# MCU.net
KiCad netlist of a schematic drawn in Altium Designer
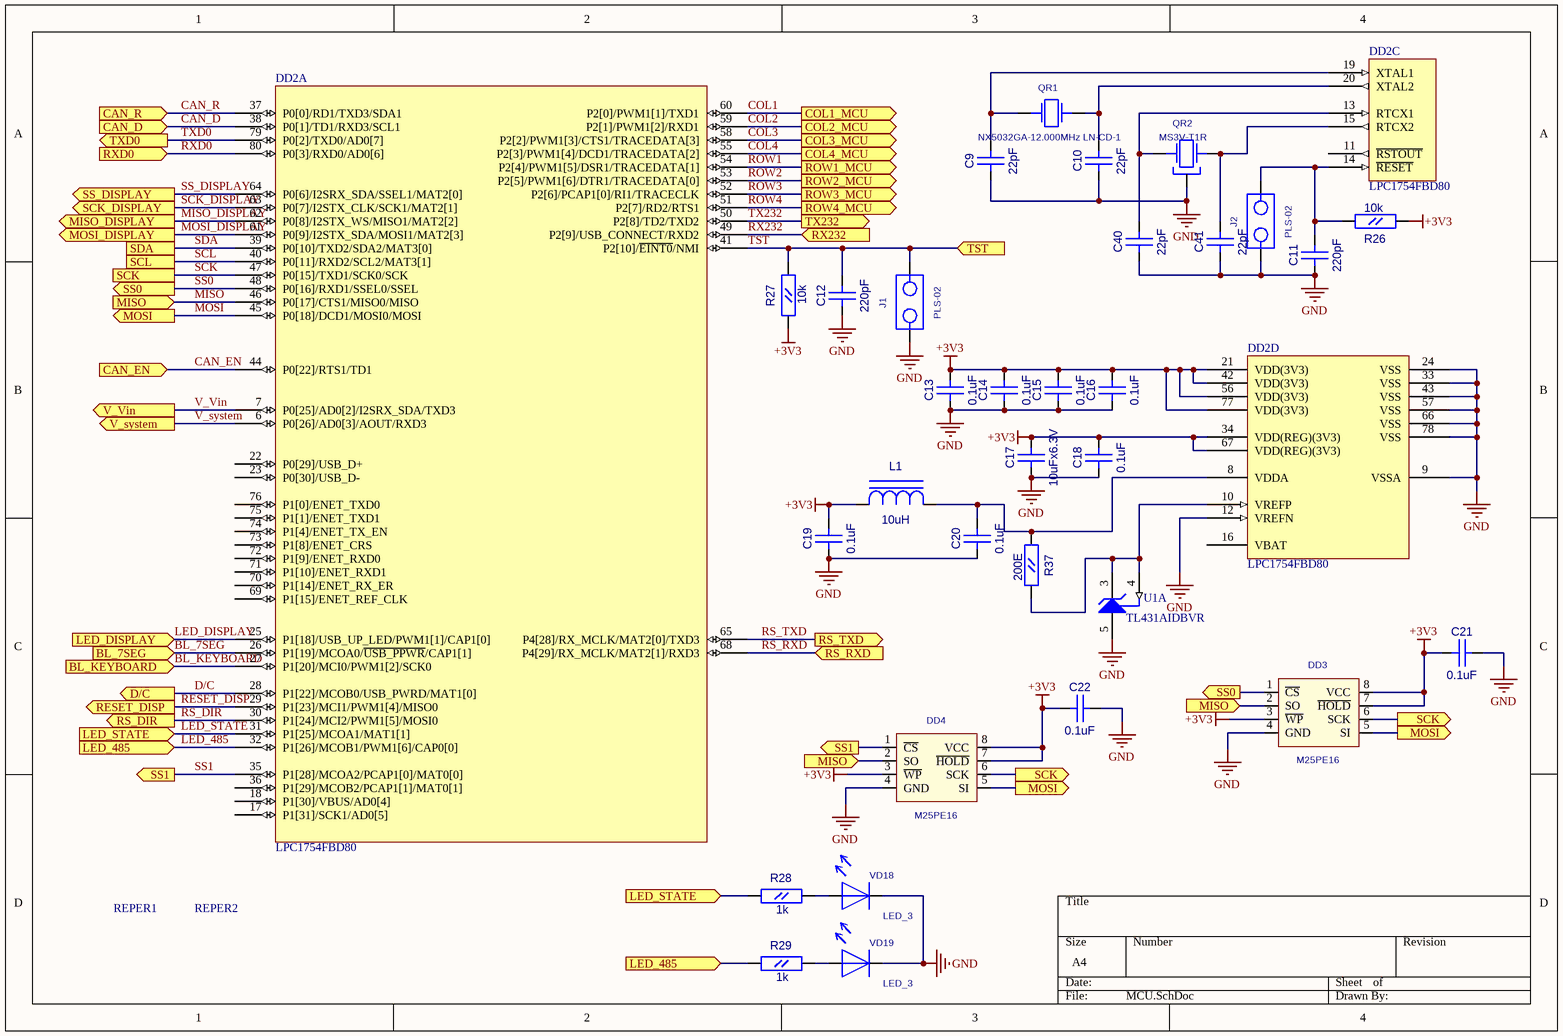
[diagram p0: MCU.SchDoc]

(export (version "E")
  (design (tool "Eeschema 10.0.6"))
  (components
    (comp (ref "C9")
      (value "22pF")
      (footprint "CC0603")
      (description "CC0603")
      (libsource (lib "gprs_modem_2") (part "CC0603"))
    )
    (comp (ref "C10")
      (value "22pF")
      (footprint "CC0603")
      (description "CC0603")
      (libsource (lib "gprs_modem_2") (part "CC0603"))
    )
    (comp (ref "C11")
      (value "220pF")
      (footprint "CC0603")
      (description "CC0603")
      (libsource (lib "gprs_modem_2") (part "CC0603"))
    )
    (comp (ref "C12")
      (value "220pF")
      (footprint "CC0603")
      (description "CC0603")
      (libsource (lib "gprs_modem_2") (part "CC0603"))
    )
    (comp (ref "C13")
      (value "0.1uF")
      (footprint "CC0603")
      (description "CC0603")
      (libsource (lib "gprs_modem_2") (part "CC0603"))
    )
    (comp (ref "C14")
      (value "0.1uF")
      (footprint "CC0603")
      (description "CC0603")
      (libsource (lib "gprs_modem_2") (part "CC0603"))
    )
    (comp (ref "C15")
      (value "0.1uF")
      (footprint "CC0603")
      (description "CC0603")
      (libsource (lib "gprs_modem_2") (part "CC0603"))
    )
    (comp (ref "C16")
      (value "0.1uF")
      (footprint "CC0603")
      (description "CC0603")
      (libsource (lib "gprs_modem_2") (part "CC0603"))
    )
    (comp (ref "C17")
      (value "10uFx6.3V")
      (footprint "CC0805")
      (description "CC0805")
      (libsource (lib "gprs_modem_2") (part "CC0805"))
    )
    (comp (ref "C18")
      (value "0.1uF")
      (footprint "CC0603")
      (description "CC0603")
      (libsource (lib "gprs_modem_2") (part "CC0603"))
    )
    (comp (ref "C19")
      (value "0.1uF")
      (footprint "CC0603")
      (description "CC0603")
      (libsource (lib "gprs_modem_2") (part "CC0603"))
    )
    (comp (ref "C20")
      (value "0.1uF")
      (footprint "CC0603")
      (description "CC0603")
      (libsource (lib "gprs_modem_2") (part "CC0603"))
    )
    (comp (ref "C21")
      (value "0.1uF")
      (footprint "CC0603")
      (description "CC0603")
      (libsource (lib "gprs_modem_2") (part "CC0603"))
    )
    (comp (ref "C22")
      (value "0.1uF")
      (footprint "CC0603")
      (description "CC0603")
      (libsource (lib "gprs_modem_2") (part "CC0603"))
    )
    (comp (ref "C40")
      (value "22pF")
      (footprint "CC0603")
      (description "CC0603")
      (libsource (lib "gprs_modem_2") (part "CC0603"))
    )
    (comp (ref "C41")
      (value "22pF")
      (footprint "CC0603")
      (description "CC0603")
      (libsource (lib "gprs_modem_2") (part "CC0603"))
    )
    (comp (ref "DD2")
      (value "LPC1754FBD80")
      (footprint "TQFP-80_0.5")
      (description "Cortex -M3 32-Bit Microcontroller, 128KB Flash, 64KB RAM, 800-Lead LQFP")
      (libsource (lib "gprs_modem_2") (part "LPC1754FBD80"))
    )
    (comp (ref "DD3")
      (value "M25PE16")
      (footprint "EIAJ_SO8")
      (description "S25FL016A0LMFI01")
      (libsource (lib "gprs_modem_2") (part "S25FL016A0LMFI01"))
    )
    (comp (ref "DD4")
      (value "M25PE16")
      (footprint "EIAJ_SO8")
      (description "S25FL016A0LMFI01")
      (libsource (lib "gprs_modem_2") (part "S25FL016A0LMFI01"))
    )
    (comp (ref "J1") (value "PLS-02") (footprint "PLS-02") (libsource (lib "gprs_modem_2") (part "PLS-02")))
    (comp (ref "J2") (value "PLS-02") (footprint "PLS-02") (libsource (lib "gprs_modem_2") (part "PLS-02")))
    (comp (ref "L1")
      (value "10uH")
      (footprint "L0603")
      (description "L0603")
      (libsource (lib "gprs_modem_2") (part "L0603"))
    )
    (comp (ref "QR1")
      (value "NX5032GA-12.000MHz LN-CD-1")
      (footprint "AC5032_2")
      (description "AC5032/2")
      (libsource (lib "gprs_modem_2") (part "AC5032_2"))
    )
    (comp (ref "QR2")
      (value "MS3V-T1R")
      (footprint "MS3V-T1R")
      (description "CRYSTAL_32768 Hz")
      (libsource (lib "gprs_modem_2") (part "MS3V-T1R"))
    )
    (comp (ref "R26")
      (value "10k")
      (footprint "RC0603")
      (description "RC0603")
      (libsource (lib "gprs_modem_2") (part "RC0603"))
    )
    (comp (ref "R27")
      (value "10k")
      (footprint "RC0603")
      (description "RC0603")
      (libsource (lib "gprs_modem_2") (part "RC0603"))
    )
    (comp (ref "R28")
      (value "1k")
      (footprint "RC0603")
      (description "RC0603")
      (libsource (lib "gprs_modem_2") (part "RC0603"))
    )
    (comp (ref "R29")
      (value "1k")
      (footprint "RC0603")
      (description "RC0603")
      (libsource (lib "gprs_modem_2") (part "RC0603"))
    )
    (comp (ref "R37")
      (value "200E")
      (footprint "RC0603")
      (description "RC0603")
      (libsource (lib "gprs_modem_2") (part "RC0603"))
    )
    (comp (ref "REPER1")
      (value "REPER1.2")
      (footprint "REPER1.2")
      (libsource (lib "gprs_modem") (part "REPER1.2"))
    )
    (comp (ref "REPER2")
      (value "REPER1.2")
      (footprint "REPER1.2")
      (libsource (lib "gprs_modem") (part "REPER1.2"))
    )
    (comp (ref "U1")
      (value "TL431AIDBVR")
      (footprint "TI-DBV5_N")
      (fields (field (name "MANUFACTURER") "Texas Instruments"))
      (libsource (lib "TI Power Management Shunt Voltage Reference") (part "TL431AIDBVR"))
    )
    (comp (ref "VD18") (value "LED_3") (footprint "LED3") (libsource (lib "gprs_modem_2") (part "LED_3")))
    (comp (ref "VD19") (value "LED_3") (footprint "LED3") (libsource (lib "gprs_modem_2") (part "LED_3")))
  )
  (nets
    (net (code "1") (name "+3V3") (class "Default")
      (node (ref "C13") (pin "2") (pinfunction "B_2") (pintype "passive"))
      (node (ref "C14") (pin "2") (pinfunction "B_2") (pintype "passive"))
      (node (ref "C15") (pin "2") (pinfunction "B_2") (pintype "passive"))
      (node (ref "C16") (pin "2") (pinfunction "B_2") (pintype "passive"))
      (node (ref "C17") (pin "2") (pinfunction "B_2") (pintype "passive"))
      (node (ref "C18") (pin "2") (pinfunction "B_2") (pintype "passive"))
      (node (ref "C19") (pin "2") (pinfunction "B_2") (pintype "passive"))
      (node (ref "C21") (pin "1") (pinfunction "A_1") (pintype "passive"))
      (node (ref "C22") (pin "1") (pinfunction "A_1") (pintype "passive"))
      (node (ref "DD2") (pin "21") (pinfunction "VDD(3V3)_21") (pintype "power_in"))
      (node (ref "DD2") (pin "34") (pinfunction "VDD(REG)(3V3)_34") (pintype "power_in"))
      (node (ref "DD2") (pin "42") (pinfunction "VDD(3V3)_42") (pintype "power_in"))
      (node (ref "DD2") (pin "56") (pinfunction "VDD(3V3)_56") (pintype "power_in"))
      (node (ref "DD2") (pin "67") (pinfunction "VDD(REG)(3V3)_67") (pintype "power_in"))
      (node (ref "DD2") (pin "77") (pinfunction "VDD(3V3)_77") (pintype "power_in"))
      (node (ref "DD3") (pin "3") (pinfunction "~{WP}_3") (pintype "passive"))
      (node (ref "DD3") (pin "7") (pinfunction "~{HOLD}_7") (pintype "passive"))
      (node (ref "DD3") (pin "8") (pinfunction "VCC_8") (pintype "passive"))
      (node (ref "DD4") (pin "3") (pinfunction "~{WP}_3") (pintype "passive"))
      (node (ref "DD4") (pin "7") (pinfunction "~{HOLD}_7") (pintype "passive"))
      (node (ref "DD4") (pin "8") (pinfunction "VCC_8") (pintype "passive"))
      (node (ref "L1") (pin "1") (pinfunction "A_1") (pintype "passive"))
      (node (ref "R26") (pin "1") (pinfunction "A_1") (pintype "passive"))
      (node (ref "R27") (pin "1") (pinfunction "A_1") (pintype "passive"))
    )
    (net (code "2") (name "/BL_7SEG") (class "Default")
      (node (ref "DD2") (pin "26") (pinfunction "P1[19]/MCOA0/~{USB_PPWR}/CAP1[1]_26") (pintype "bidirectional"))
    )
    (net (code "3") (name "/BL_KEYBOARD") (class "Default")
      (node (ref "DD2") (pin "27") (pinfunction "P1[20]/MCI0/PWM1[2]/SCK0_27") (pintype "bidirectional"))
    )
    (net (code "4") (name "/CAN_D") (class "Default")
      (node (ref "DD2") (pin "38") (pinfunction "P0[1]/TD1/RXD3/SCL1_38") (pintype "bidirectional"))
    )
    (net (code "5") (name "/CAN_EN") (class "Default")
      (node (ref "DD2") (pin "44") (pinfunction "P0[22]/RTS1/TD1_44") (pintype "bidirectional"))
    )
    (net (code "6") (name "/CAN_R") (class "Default")
      (node (ref "DD2") (pin "37") (pinfunction "P0[0]/RD1/TXD3/SDA1_37") (pintype "bidirectional"))
    )
    (net (code "7") (name "/COL1") (class "Default")
      (node (ref "DD2") (pin "60") (pinfunction "P2[0]/PWM1[1]/TXD1_60") (pintype "bidirectional"))
    )
    (net (code "8") (name "/COL2") (class "Default")
      (node (ref "DD2") (pin "59") (pinfunction "P2[1]/PWM1[2]/RXD1_59") (pintype "bidirectional"))
    )
    (net (code "9") (name "/COL3") (class "Default")
      (node (ref "DD2") (pin "58") (pinfunction "P2[2]/PWM1[3]/CTS1/TRACEDATA[3]_58") (pintype "bidirectional"))
    )
    (net (code "10") (name "/COL4") (class "Default")
      (node (ref "DD2") (pin "55") (pinfunction "P2[3]/PWM1[4]/DCD1/TRACEDATA[2]_55") (pintype "bidirectional"))
    )
    (net (code "11") (name "/D{slash}C") (class "Default")
      (node (ref "DD2") (pin "28") (pinfunction "P1[22]/MCOB0/USB_PWRD/MAT1[0]_28") (pintype "bidirectional"))
    )
    (net (code "12") (name "/LED_485") (class "Default")
      (node (ref "DD2") (pin "32") (pinfunction "P1[26]/MCOB1/PWM1[6]/CAP0[0]_32") (pintype "bidirectional"))
      (node (ref "R29") (pin "1") (pinfunction "A_1") (pintype "passive"))
    )
    (net (code "13") (name "/LED_DISPLAY") (class "Default")
      (node (ref "DD2") (pin "25") (pinfunction "P1[18]/USB_UP_LED/PWM1[1]/CAP1[0]_25") (pintype "bidirectional"))
    )
    (net (code "14") (name "/LED_STATE") (class "Default")
      (node (ref "DD2") (pin "31") (pinfunction "P1[25]/MCOA1/MAT1[1]_31") (pintype "bidirectional"))
      (node (ref "R28") (pin "1") (pinfunction "A_1") (pintype "passive"))
    )
    (net (code "15") (name "/MISO") (class "Default")
      (node (ref "DD2") (pin "46") (pinfunction "P0[17]/CTS1/MISO0/MISO_46") (pintype "bidirectional"))
      (node (ref "DD3") (pin "2") (pinfunction "SO_2") (pintype "passive"))
      (node (ref "DD4") (pin "2") (pinfunction "SO_2") (pintype "passive"))
    )
    (net (code "16") (name "/MISO_DISPLAY") (class "Default")
      (node (ref "DD2") (pin "62") (pinfunction "P0[8]/I2STX_WS/MISO1/MAT2[2]_62") (pintype "bidirectional"))
    )
    (net (code "17") (name "/MOSI") (class "Default")
      (node (ref "DD2") (pin "45") (pinfunction "P0[18]/DCD1/MOSI0/MOSI_45") (pintype "bidirectional"))
      (node (ref "DD3") (pin "5") (pinfunction "SI_5") (pintype "passive"))
      (node (ref "DD4") (pin "5") (pinfunction "SI_5") (pintype "passive"))
    )
    (net (code "18") (name "/MOSI_DISPLAY") (class "Default")
      (node (ref "DD2") (pin "61") (pinfunction "P0[9]/I2STX_SDA/MOSI1/MAT2[3]_61") (pintype "bidirectional"))
    )
    (net (code "19") (name "/RESET_DISP") (class "Default")
      (node (ref "DD2") (pin "29") (pinfunction "P1[23]/MCI1/PWM1[4]/MISO0_29") (pintype "bidirectional"))
    )
    (net (code "20") (name "/ROW1") (class "Default")
      (node (ref "DD2") (pin "54") (pinfunction "P2[4]/PWM1[5]/DSR1/TRACEDATA[1]_54") (pintype "bidirectional"))
    )
    (net (code "21") (name "/ROW2") (class "Default")
      (node (ref "DD2") (pin "53") (pinfunction "P2[5]/PWM1[6]/DTR1/TRACEDATA[0]_53") (pintype "bidirectional"))
    )
    (net (code "22") (name "/ROW3") (class "Default")
      (node (ref "DD2") (pin "52") (pinfunction "P2[6]/PCAP1[0]/RI1/TRACECLK_52") (pintype "bidirectional"))
    )
    (net (code "23") (name "/ROW4") (class "Default")
      (node (ref "DD2") (pin "51") (pinfunction "P2[7]/RD2/RTS1_51") (pintype "bidirectional"))
    )
    (net (code "24") (name "/RS_DIR") (class "Default")
      (node (ref "DD2") (pin "30") (pinfunction "P1[24]/MCI2/PWM1[5]/MOSI0_30") (pintype "bidirectional"))
    )
    (net (code "25") (name "/RS_RXD") (class "Default")
      (node (ref "DD2") (pin "68") (pinfunction "P4[29]/RX_MCLK/MAT2[1]/RXD3_68") (pintype "bidirectional"))
    )
    (net (code "26") (name "/RS_TXD") (class "Default")
      (node (ref "DD2") (pin "65") (pinfunction "P4[28]/RX_MCLK/MAT2[0]/TXD3_65") (pintype "bidirectional"))
    )
    (net (code "27") (name "/RX232") (class "Default")
      (node (ref "DD2") (pin "49") (pinfunction "P2[9]/USB_CONNECT/RXD2_49") (pintype "bidirectional"))
    )
    (net (code "28") (name "/RXD0") (class "Default")
      (node (ref "DD2") (pin "80") (pinfunction "P0[3]/RXD0/AD0[6]_80") (pintype "bidirectional"))
    )
    (net (code "29") (name "/SCK") (class "Default")
      (node (ref "DD2") (pin "47") (pinfunction "P0[15]/TXD1/SCK0/SCK_47") (pintype "bidirectional"))
      (node (ref "DD3") (pin "6") (pinfunction "SCK_6") (pintype "passive"))
      (node (ref "DD4") (pin "6") (pinfunction "SCK_6") (pintype "passive"))
    )
    (net (code "30") (name "/SCK_DISPLAY") (class "Default")
      (node (ref "DD2") (pin "63") (pinfunction "P0[7]/I2STX_CLK/SCK1/MAT2[1]_63") (pintype "bidirectional"))
    )
    (net (code "31") (name "/SCL") (class "Default")
      (node (ref "DD2") (pin "40") (pinfunction "P0[11]/RXD2/SCL2/MAT3[1]_40") (pintype "bidirectional"))
    )
    (net (code "32") (name "/SDA") (class "Default")
      (node (ref "DD2") (pin "39") (pinfunction "P0[10]/TXD2/SDA2/MAT3[0]_39") (pintype "bidirectional"))
    )
    (net (code "33") (name "/SS0") (class "Default")
      (node (ref "DD2") (pin "48") (pinfunction "P0[16]/RXD1/SSEL0/SSEL_48") (pintype "bidirectional"))
      (node (ref "DD3") (pin "1") (pinfunction "~{CS}_1") (pintype "passive"))
    )
    (net (code "34") (name "/SS1") (class "Default")
      (node (ref "DD2") (pin "35") (pinfunction "P1[28]/MCOA2/PCAP1[0]/MAT0[0]_35") (pintype "bidirectional"))
      (node (ref "DD4") (pin "1") (pinfunction "~{CS}_1") (pintype "passive"))
    )
    (net (code "35") (name "/SS_DISPLAY") (class "Default")
      (node (ref "DD2") (pin "64") (pinfunction "P0[6]/I2SRX_SDA/SSEL1/MAT2[0]_64") (pintype "bidirectional"))
    )
    (net (code "36") (name "/TST") (class "Default")
      (node (ref "C12") (pin "2") (pinfunction "B_2") (pintype "passive"))
      (node (ref "DD2") (pin "41") (pinfunction "P2[10]/~{EINT0}/NMI_41") (pintype "bidirectional"))
      (node (ref "J1") (pin "2") (pintype "passive"))
      (node (ref "R27") (pin "2") (pinfunction "B_2") (pintype "passive"))
    )
    (net (code "37") (name "/TX232") (class "Default")
      (node (ref "DD2") (pin "50") (pinfunction "P2[8]/TD2/TXD2_50") (pintype "bidirectional"))
    )
    (net (code "38") (name "/TXD0") (class "Default")
      (node (ref "DD2") (pin "79") (pinfunction "P0[2]/TXD0/AD0[7]_79") (pintype "bidirectional"))
    )
    (net (code "39") (name "/V_Vin") (class "Default")
      (node (ref "DD2") (pin "7") (pinfunction "P0[25]/AD0[2]/I2SRX_SDA/TXD3_7") (pintype "bidirectional"))
    )
    (net (code "40") (name "/V_system") (class "Default")
      (node (ref "DD2") (pin "6") (pinfunction "P0[26]/AD0[3]/AOUT/RXD3_6") (pintype "bidirectional"))
    )
    (net (code "41") (name "GND") (class "Default")
      (node (ref "C10") (pin "1") (pinfunction "A_1") (pintype "passive"))
      (node (ref "C11") (pin "1") (pinfunction "A_1") (pintype "passive"))
      (node (ref "C12") (pin "1") (pinfunction "A_1") (pintype "passive"))
      (node (ref "C13") (pin "1") (pinfunction "A_1") (pintype "passive"))
      (node (ref "C14") (pin "1") (pinfunction "A_1") (pintype "passive"))
      (node (ref "C15") (pin "1") (pinfunction "A_1") (pintype "passive"))
      (node (ref "C16") (pin "1") (pinfunction "A_1") (pintype "passive"))
      (node (ref "C17") (pin "1") (pinfunction "A_1") (pintype "passive"))
      (node (ref "C18") (pin "1") (pinfunction "A_1") (pintype "passive"))
      (node (ref "C19") (pin "1") (pinfunction "A_1") (pintype "passive"))
      (node (ref "C20") (pin "1") (pinfunction "A_1") (pintype "passive"))
      (node (ref "C21") (pin "2") (pinfunction "B_2") (pintype "passive"))
      (node (ref "C22") (pin "2") (pinfunction "B_2") (pintype "passive"))
      (node (ref "C40") (pin "1") (pinfunction "A_1") (pintype "passive"))
      (node (ref "C41") (pin "1") (pinfunction "A_1") (pintype "passive"))
      (node (ref "C9") (pin "1") (pinfunction "A_1") (pintype "passive"))
      (node (ref "DD2") (pin "12") (pinfunction "VREFN_12") (pintype "input"))
      (node (ref "DD2") (pin "24") (pinfunction "VSS_24") (pintype "power_in"))
      (node (ref "DD2") (pin "33") (pinfunction "VSS_33") (pintype "power_in"))
      (node (ref "DD2") (pin "43") (pinfunction "VSS_43") (pintype "power_in"))
      (node (ref "DD2") (pin "57") (pinfunction "VSS_57") (pintype "power_in"))
      (node (ref "DD2") (pin "66") (pinfunction "VSS_66") (pintype "power_in"))
      (node (ref "DD2") (pin "78") (pinfunction "VSS_78") (pintype "power_in"))
      (node (ref "DD2") (pin "9") (pinfunction "VSSA_9") (pintype "power_in"))
      (node (ref "DD3") (pin "4") (pinfunction "GND_4") (pintype "passive"))
      (node (ref "DD4") (pin "4") (pinfunction "GND_4") (pintype "passive"))
      (node (ref "J1") (pin "1") (pintype "passive"))
      (node (ref "J2") (pin "1") (pintype "passive"))
      (node (ref "QR2") (pin "3") (pinfunction "3_3") (pintype "passive"))
      (node (ref "U1") (pin "5") (pinfunction "ANODE_5") (pintype "passive"))
      (node (ref "VD18") (pin "1") (pintype "passive"))
      (node (ref "VD19") (pin "1") (pintype "passive"))
    )
    (net (code "42") (name "Net-(C9-B)") (class "Default")
      (node (ref "C9") (pin "2") (pinfunction "B_2") (pintype "passive"))
      (node (ref "DD2") (pin "19") (pinfunction "XTAL1_19") (pintype "input"))
      (node (ref "QR1") (pin "1") (pintype "passive"))
    )
    (net (code "43") (name "Net-(C10-B)") (class "Default")
      (node (ref "C10") (pin "2") (pinfunction "B_2") (pintype "passive"))
      (node (ref "DD2") (pin "20") (pinfunction "XTAL2_20") (pintype "output"))
      (node (ref "QR1") (pin "2") (pintype "passive"))
    )
    (net (code "44") (name "Net-(C11-B)") (class "Default")
      (node (ref "C11") (pin "2") (pinfunction "B_2") (pintype "passive"))
      (node (ref "DD2") (pin "14") (pinfunction "~{RESET}_14") (pintype "input"))
      (node (ref "J2") (pin "2") (pintype "passive"))
      (node (ref "R26") (pin "2") (pinfunction "B_2") (pintype "passive"))
    )
    (net (code "45") (name "Net-(C20-B)") (class "Default")
      (node (ref "C20") (pin "2") (pinfunction "B_2") (pintype "passive"))
      (node (ref "DD2") (pin "8") (pinfunction "VDDA_8") (pintype "power_in"))
      (node (ref "L1") (pin "2") (pinfunction "C_2") (pintype "passive"))
      (node (ref "R37") (pin "1") (pinfunction "A_1") (pintype "passive"))
    )
    (net (code "46") (name "Net-(C40-B)") (class "Default")
      (node (ref "C40") (pin "2") (pinfunction "B_2") (pintype "passive"))
      (node (ref "DD2") (pin "13") (pinfunction "RTCX1_13") (pintype "input"))
      (node (ref "QR2") (pin "2") (pinfunction "X2_2") (pintype "passive"))
    )
    (net (code "47") (name "Net-(C41-B)") (class "Default")
      (node (ref "C41") (pin "2") (pinfunction "B_2") (pintype "passive"))
      (node (ref "DD2") (pin "15") (pinfunction "RTCX2_15") (pintype "output"))
      (node (ref "QR2") (pin "1") (pinfunction "X1_1") (pintype "passive"))
    )
    (net (code "48") (name "Net-(DD2D-VREFP)") (class "Default")
      (node (ref "DD2") (pin "10") (pinfunction "VREFP_10") (pintype "input"))
      (node (ref "R37") (pin "2") (pinfunction "B_2") (pintype "passive"))
      (node (ref "U1") (pin "3") (pinfunction "CATHODE_3") (pintype "passive"))
      (node (ref "U1") (pin "4") (pinfunction "REF_4") (pintype "input"))
    )
    (net (code "49") (name "Net-(R28-B)") (class "Default")
      (node (ref "R28") (pin "2") (pinfunction "B_2") (pintype "passive"))
      (node (ref "VD18") (pin "2") (pintype "passive"))
    )
    (net (code "50") (name "Net-(R29-B)") (class "Default")
      (node (ref "R29") (pin "2") (pinfunction "B_2") (pintype "passive"))
      (node (ref "VD19") (pin "2") (pintype "passive"))
    )
    (net (code "51") (name "unconnected-(DD2A-P0[29]{slash}USB_D+-Pad22)") (class "Default")
      (node (ref "DD2") (pin "22") (pinfunction "P0[29]/USB_D+_22") (pintype "bidirectional"))
    )
    (net (code "52") (name "unconnected-(DD2A-P0[30]{slash}USB_D--Pad23)") (class "Default")
      (node (ref "DD2") (pin "23") (pinfunction "P0[30]/USB_D-_23") (pintype "bidirectional"))
    )
    (net (code "53") (name "unconnected-(DD2A-P1[0]{slash}ENET_TXD0-Pad76)") (class "Default")
      (node (ref "DD2") (pin "76") (pinfunction "P1[0]/ENET_TXD0_76") (pintype "bidirectional"))
    )
    (net (code "54") (name "unconnected-(DD2A-P1[1]{slash}ENET_TXD1-Pad75)") (class "Default")
      (node (ref "DD2") (pin "75") (pinfunction "P1[1]/ENET_TXD1_75") (pintype "bidirectional"))
    )
    (net (code "55") (name "unconnected-(DD2A-P1[4]{slash}ENET_TX_EN-Pad74)") (class "Default")
      (node (ref "DD2") (pin "74") (pinfunction "P1[4]/ENET_TX_EN_74") (pintype "bidirectional"))
    )
    (net (code "56") (name "unconnected-(DD2A-P1[8]{slash}ENET_CRS-Pad73)") (class "Default")
      (node (ref "DD2") (pin "73") (pinfunction "P1[8]/ENET_CRS_73") (pintype "bidirectional"))
    )
    (net (code "57") (name "unconnected-(DD2A-P1[9]{slash}ENET_RXD0-Pad72)") (class "Default")
      (node (ref "DD2") (pin "72") (pinfunction "P1[9]/ENET_RXD0_72") (pintype "bidirectional"))
    )
    (net (code "58") (name "unconnected-(DD2A-P1[10]{slash}ENET_RXD1-Pad71)") (class "Default")
      (node (ref "DD2") (pin "71") (pinfunction "P1[10]/ENET_RXD1_71") (pintype "bidirectional"))
    )
    (net (code "59") (name "unconnected-(DD2A-P1[14]{slash}ENET_RX_ER-Pad70)") (class "Default")
      (node (ref "DD2") (pin "70") (pinfunction "P1[14]/ENET_RX_ER_70") (pintype "bidirectional"))
    )
    (net (code "60") (name "unconnected-(DD2A-P1[15]{slash}ENET_REF_CLK-Pad69)") (class "Default")
      (node (ref "DD2") (pin "69") (pinfunction "P1[15]/ENET_REF_CLK_69") (pintype "bidirectional"))
    )
    (net (code "61") (name "unconnected-(DD2A-P1[29]{slash}MCOB2{slash}PCAP1[1]{slash}MAT0[1]-Pad36)") (class "Default")
      (node (ref "DD2") (pin "36") (pinfunction "P1[29]/MCOB2/PCAP1[1]/MAT0[1]_36") (pintype "bidirectional"))
    )
    (net (code "62") (name "unconnected-(DD2A-P1[30]{slash}VBUS{slash}AD0[4]-Pad18)") (class "Default")
      (node (ref "DD2") (pin "18") (pinfunction "P1[30]/VBUS/AD0[4]_18") (pintype "bidirectional"))
    )
    (net (code "63") (name "unconnected-(DD2A-P1[31]{slash}SCK1{slash}AD0[5]-Pad17)") (class "Default")
      (node (ref "DD2") (pin "17") (pinfunction "P1[31]/SCK1/AD0[5]_17") (pintype "bidirectional"))
    )
    (net (code "64") (name "unconnected-(DD2C-~{RSTOUT}-Pad11)") (class "Default")
      (node (ref "DD2") (pin "11") (pinfunction "~{RSTOUT}_11") (pintype "output"))
    )
    (net (code "65") (name "unconnected-(DD2D-VBAT-Pad16)") (class "Default")
      (node (ref "DD2") (pin "16") (pinfunction "VBAT_16") (pintype "power_in"))
    )
    (net (code "66") (name "unconnected-(REPER1-Pad1)") (class "Default")
      (node (ref "REPER1") (pin "1") (pintype "passive"))
    )
    (net (code "67") (name "unconnected-(REPER2-Pad1)") (class "Default")
      (node (ref "REPER2") (pin "1") (pintype "passive"))
    )
  )
)
